# Buck.net
KiCad netlist of a schematic drawn in Altium Designer
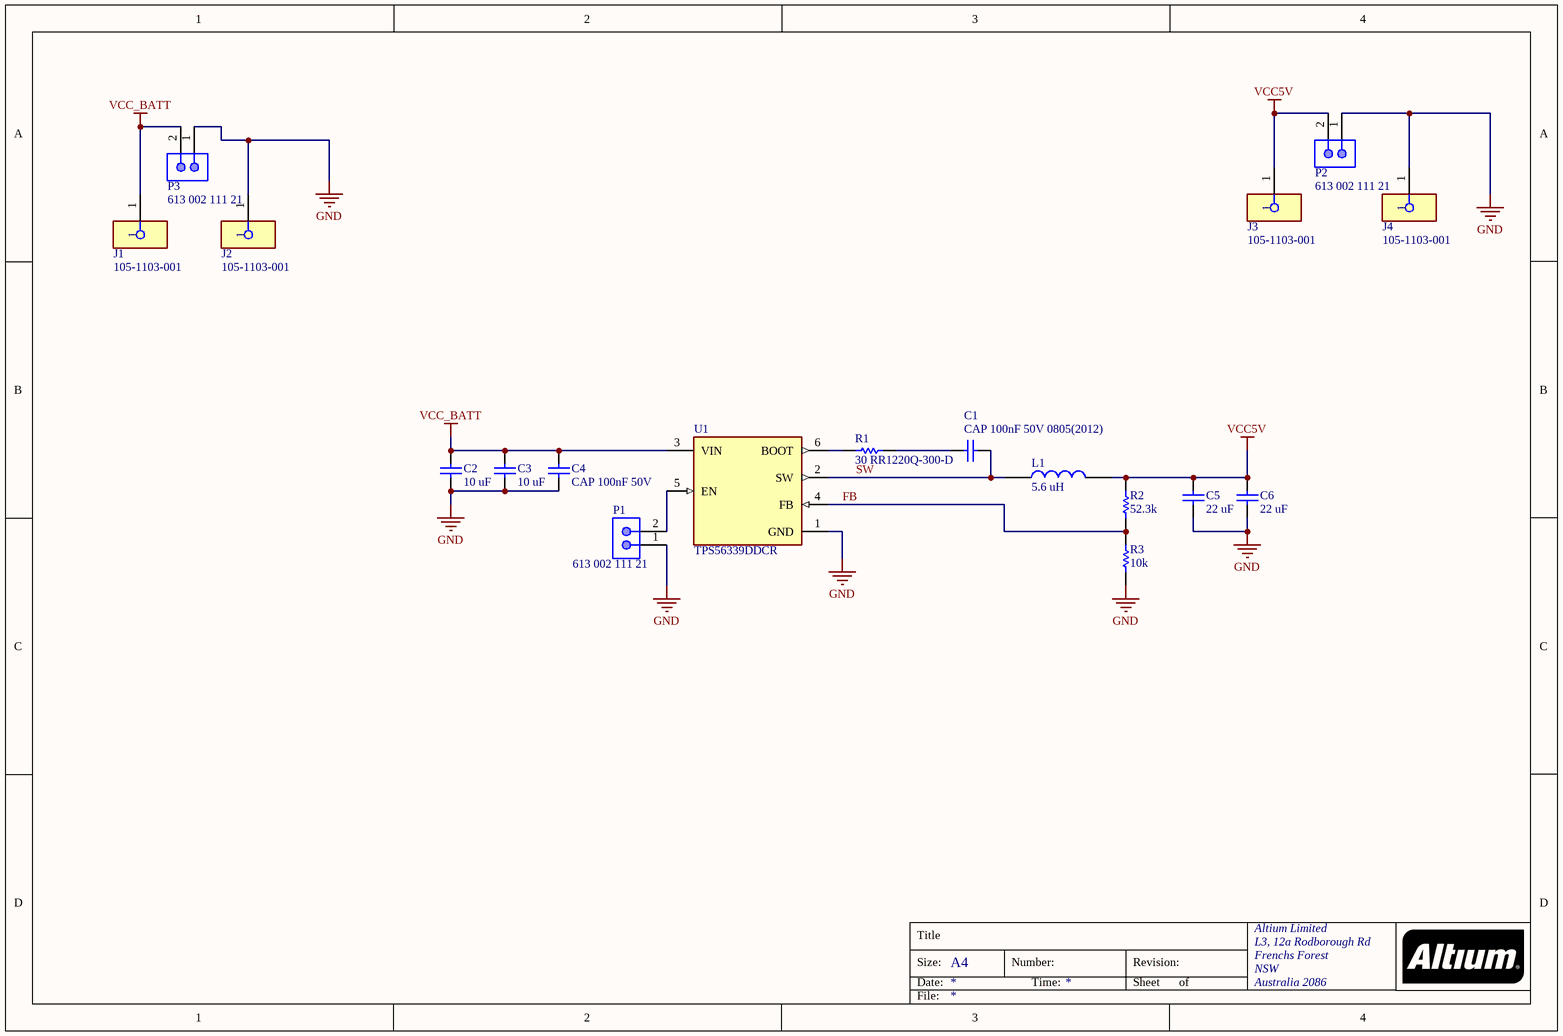
[diagram p0: Buck.SchDoc]

(export (version "E")
  (design (tool "Eeschema 10.0.6"))
  (components
    (comp (ref "C1")
      (value "CAP 100nF 50V 0805(2012)")
      (footprint "CAPC0805(2012)100_M")
      (description "CAP 100nF 50V ±20% 0805 (2012 Metric) Thickness 1mm SMD")
      (fields (field (name "TOLERANCE") "Â±20%"))
      (libsource (lib "Altium Content Vault") (part "CAP"))
    )
    (comp (ref "C2")
      (value "10 uF")
      (footprint "CAPC1608X100X20VL10T10")
      (description "Chip Capacitor, 10 uF, +/- 20%, 25 V, -55 to 85 degC, 0603 (1608 Metric), RoHS, Tape and Reel")
      (fields (field (name "MANUFACTURER") "TDK") (field (name "TOLERANCE") "±20%"))
      (libsource (lib "Altium Content Vault") (part "CAP-NP-2"))
    )
    (comp (ref "C3")
      (value "10 uF")
      (footprint "CAPC1608X100X20VL10T10")
      (description "Chip Capacitor, 10 uF, +/- 20%, 25 V, -55 to 85 degC, 0603 (1608 Metric), RoHS, Tape and Reel")
      (fields (field (name "MANUFACTURER") "TDK") (field (name "TOLERANCE") "±20%"))
      (libsource (lib "Altium Content Vault") (part "CAP-NP-2"))
    )
    (comp (ref "C4")
      (value "CAP 100nF 50V")
      (footprint "CAPC0805(2012)100_M")
      (description "CAP 100nF 50V ±20% 0805 (2012 Metric) Thickness 1mm SMD")
      (fields (field (name "TOLERANCE") "Â±20%"))
      (libsource (lib "Altium Content Vault") (part "CAP"))
    )
    (comp (ref "C5")
      (value "22 uF")
      (footprint "CAPC3225X279X50LL20T25")
      (description "Chip Capacitor, 22 uF, +/- 20%, 25 V, -55 to 85 degC, 1210 (3225 Metric), RoHS, Tape and Reel")
      (fields (field (name "MANUFACTURER") "AVX"))
      (libsource (lib "Altium Content Vault") (part "CAP-NP-2"))
    )
    (comp (ref "C6")
      (value "22 uF")
      (footprint "CAPC3225X279X50LL20T25")
      (description "Chip Capacitor, 22 uF, +/- 20%, 25 V, -55 to 85 degC, 1210 (3225 Metric), RoHS, Tape and Reel")
      (fields (field (name "MANUFACTURER") "AVX"))
      (libsource (lib "Altium Content Vault") (part "CAP-NP-2"))
    )
    (comp (ref "J1")
      (value "105-1103-001")
      (footprint "FP-105-1103-001-MFG")
      (description "CONN TIP JACK SOLDER BLACK")
      (fields
        (field (name "MANUFACTURER") "Bel Fuse")
        (field (name "OCTOPART") "https://octopart.com/105-1103-001-bel+fuse-73381038")
      )
      (libsource (lib "Altium Content Vault") (part "98815daf2f2c152b0c43f5ab9800df6"))
    )
    (comp (ref "J2")
      (value "105-1103-001")
      (footprint "FP-105-1103-001-MFG")
      (description "CONN TIP JACK SOLDER BLACK")
      (fields
        (field (name "MANUFACTURER") "Bel Fuse")
        (field (name "OCTOPART") "https://octopart.com/105-1103-001-bel+fuse-73381038")
      )
      (libsource (lib "Altium Content Vault") (part "98815daf2f2c152b0c43f5ab9800df6"))
    )
    (comp (ref "J3")
      (value "105-1103-001")
      (footprint "FP-105-1103-001-MFG")
      (description "CONN TIP JACK SOLDER BLACK")
      (fields
        (field (name "MANUFACTURER") "Bel Fuse")
        (field (name "OCTOPART") "https://octopart.com/105-1103-001-bel+fuse-73381038")
      )
      (libsource (lib "Altium Content Vault") (part "98815daf2f2c152b0c43f5ab9800df6"))
    )
    (comp (ref "J4")
      (value "105-1103-001")
      (footprint "FP-105-1103-001-MFG")
      (description "CONN TIP JACK SOLDER BLACK")
      (fields
        (field (name "MANUFACTURER") "Bel Fuse")
        (field (name "OCTOPART") "https://octopart.com/105-1103-001-bel+fuse-73381038")
      )
      (libsource (lib "Altium Content Vault") (part "98815daf2f2c152b0c43f5ab9800df6"))
    )
    (comp (ref "L1")
      (value "5.6 uH")
      (footprint "470")
      (libsource (lib "SRP6540-5R6M") (part "SRP6540-5R6M"))
    )
    (comp (ref "P1")
      (value "613 002 111 21")
      (footprint "WE-61300211121_V")
      (libsource (lib "") (part "CN-1P-M-R2_1"))
    )
    (comp (ref "P2")
      (value "613 002 111 21")
      (footprint "WE-61300211121_V")
      (libsource (lib "Altium Content Vault") (part "CN-1P-M-R2"))
    )
    (comp (ref "P3")
      (value "613 002 111 21")
      (footprint "WE-61300211121_V")
      (libsource (lib "Altium Content Vault") (part "CN-1P-M-R2"))
    )
    (comp (ref "R1")
      (value "30 RR1220Q-300-D")
      (footprint "RESC2013X50X40LL20T20")
      (fields (field (name "PART NUMBER") "RR1220Q-300-D") (field (name "MANUFACTURER") "Susumu"))
      (libsource (lib "Altium Content Vault") (part "RES"))
    )
    (comp (ref "R2")
      (value "52.3k")
      (footprint "RESC1609X50X30LL10T20")
      (fields (field (name "PART NUMBER") "CRCW060352K3FKEA") (field (name "MANUFACTURER") "Vishay Dale"))
      (libsource (lib "Altium Content Vault") (part "RES"))
    )
    (comp (ref "R3")
      (value "10k")
      (footprint "RESC1609X50X30NL8T20")
      (description "Chip Resistor, 10 KOhm, +/- 1%, 100 mW, -55 to 155 degC, 0603 (1608 Metric), RoHS, Tape and Reel")
      (fields (field (name "MANUFACTURER") "Vishay Semiconductor"))
      (libsource (lib "Altium Content Vault") (part "RES-2"))
    )
    (comp (ref "U1")
      (value "TPS56339DDCR")
      (footprint "FP-DDC0006A-MFG")
      (description "PWR MGMT SPECIALIZED REGULATOR")
      (fields
        (field (name "MANUFACTURER") "Texas Instruments")
        (field (name "OCTOPART") "https://octopart.com/tps56339ddcr-texas+instruments-101466410")
      )
      (libsource (lib "Altium Content Vault") (part "2ef13c8a92b2ccd2de8c1984d71b5d5"))
    )
  )
  (nets
    (net (code "1") (name "/FB") (class "Default")
      (node (ref "R2") (pin "1") (pinfunction "1_1") (pintype "passive"))
      (node (ref "R3") (pin "2") (pinfunction "2_2") (pintype "passive"))
      (node (ref "U1") (pin "4") (pinfunction "FB_4") (pintype "input"))
    )
    (net (code "2") (name "/SW") (class "Default")
      (node (ref "C1") (pin "1") (pinfunction "1_1") (pintype "passive"))
      (node (ref "L1") (pin "1") (pinfunction "1_1") (pintype "passive"))
      (node (ref "U1") (pin "2") (pinfunction "SW_2") (pintype "output"))
    )
    (net (code "3") (name "GND") (class "Default")
      (node (ref "C2") (pin "1") (pinfunction "1_1") (pintype "passive"))
      (node (ref "C3") (pin "1") (pinfunction "1_1") (pintype "passive"))
      (node (ref "C4") (pin "1") (pinfunction "1_1") (pintype "passive"))
      (node (ref "C5") (pin "1") (pinfunction "1_1") (pintype "passive"))
      (node (ref "C6") (pin "1") (pinfunction "1_1") (pintype "passive"))
      (node (ref "J2") (pin "1") (pinfunction "1_1") (pintype "passive"))
      (node (ref "J4") (pin "1") (pinfunction "1_1") (pintype "passive"))
      (node (ref "P1") (pin "1") (pinfunction "1_1") (pintype "passive"))
      (node (ref "P2") (pin "1") (pinfunction "1_1") (pintype "passive"))
      (node (ref "P3") (pin "1") (pinfunction "1_1") (pintype "passive"))
      (node (ref "R3") (pin "1") (pinfunction "1_1") (pintype "passive"))
      (node (ref "U1") (pin "1") (pinfunction "GND_1") (pintype "power_in"))
    )
    (net (code "4") (name "Net-(C1-Pad2)") (class "Default")
      (node (ref "C1") (pin "2") (pinfunction "2_2") (pintype "passive"))
      (node (ref "R1") (pin "2") (pinfunction "2_2") (pintype "passive"))
    )
    (net (code "5") (name "Net-(U1-BOOT)") (class "Default")
      (node (ref "R1") (pin "1") (pinfunction "1_1") (pintype "passive"))
      (node (ref "U1") (pin "6") (pinfunction "BOOT_6") (pintype "output"))
    )
    (net (code "6") (name "Net-(U1-EN)") (class "Default")
      (node (ref "P1") (pin "2") (pinfunction "2_2") (pintype "passive"))
      (node (ref "U1") (pin "5") (pinfunction "EN_5") (pintype "input"))
    )
    (net (code "7") (name "VCC5V") (class "Default")
      (node (ref "C5") (pin "2") (pinfunction "2_2") (pintype "passive"))
      (node (ref "C6") (pin "2") (pinfunction "2_2") (pintype "passive"))
      (node (ref "J3") (pin "1") (pinfunction "1_1") (pintype "passive"))
      (node (ref "L1") (pin "2") (pinfunction "2_2") (pintype "passive"))
      (node (ref "P2") (pin "2") (pinfunction "2_2") (pintype "passive"))
      (node (ref "R2") (pin "2") (pinfunction "2_2") (pintype "passive"))
    )
    (net (code "8") (name "VCC_BATT") (class "Default")
      (node (ref "C2") (pin "2") (pinfunction "2_2") (pintype "passive"))
      (node (ref "C3") (pin "2") (pinfunction "2_2") (pintype "passive"))
      (node (ref "C4") (pin "2") (pinfunction "2_2") (pintype "passive"))
      (node (ref "J1") (pin "1") (pinfunction "1_1") (pintype "passive"))
      (node (ref "P3") (pin "2") (pinfunction "2_2") (pintype "passive"))
      (node (ref "U1") (pin "3") (pinfunction "VIN_3") (pintype "power_in"))
    )
  )
)
